# Singularitron_SD_Card_Module.net
KiCad netlist of a schematic drawn in EAGLE
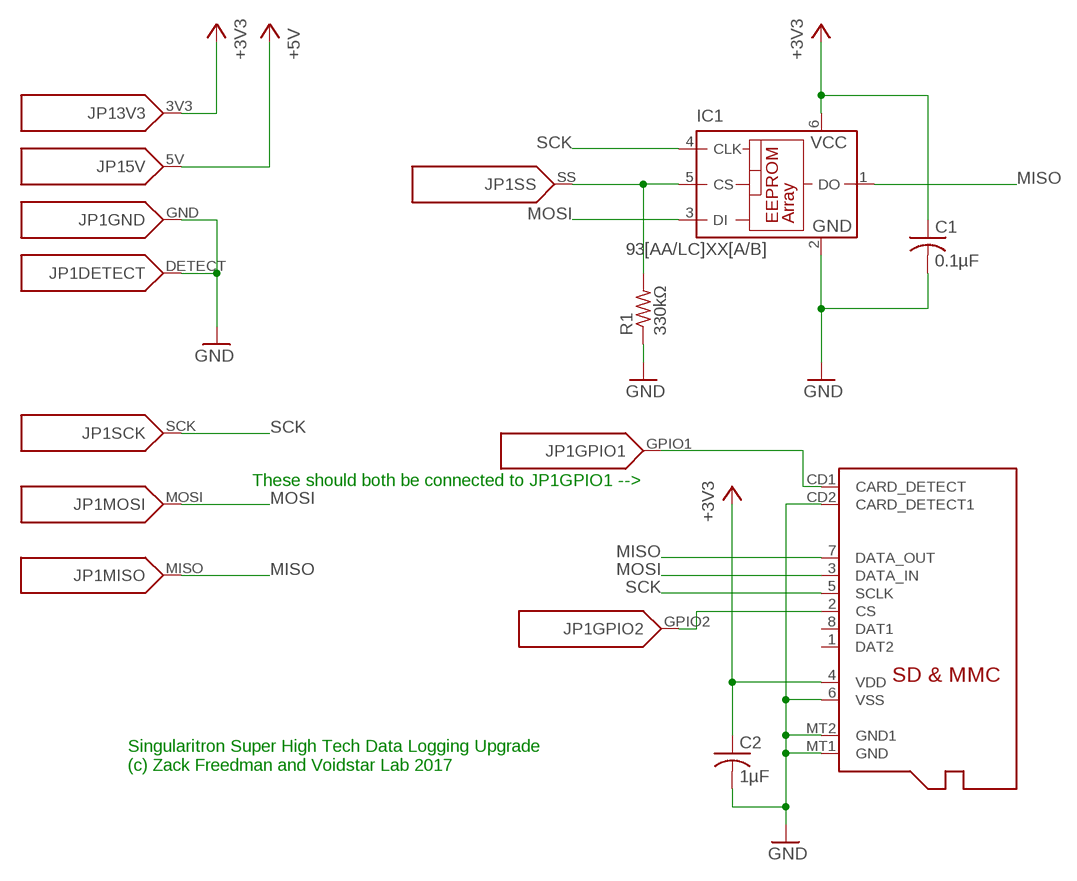
[diagram p0: schematic, sheet 1]

(export (version "E")
  (design (tool "Eeschema 10.0.6"))
  (components
    (comp (ref "C1")
      (value "0.1µF")
      (footprint "eagle-import:C0603")
      (libsource (lib "eagle-import") (part "C-USC0603"))
    )
    (comp (ref "C2")
      (value "1µF")
      (footprint "eagle-import:C0603")
      (libsource (lib "eagle-import") (part "C-USC0603"))
    )
    (comp (ref "IC1")
      (value "93[AA/LC]XX[A/B]")
      (footprint "eagle-import:SOT23-6")
      (fields (field (name "MPN") "93AA76AT-I/OT"))
      (libsource (lib "eagle-import") (part "9376?AAA"))
    )
    (comp (ref "JP1")
      (value "SINGULARITRON_CART_BASE")
      (footprint "eagle-import:SINGULARITRON_CART_BASE")
      (libsource (lib "eagle-import") (part "SINGULARITRON_CART_BASE"))
    )
    (comp (ref "JP2")
      (value "MICROSD")
      (footprint "eagle-import:MICROSD")
      (libsource (lib "eagle-import") (part "MICROSD"))
    )
    (comp (ref "R1")
      (value "330kΩ")
      (footprint "eagle-import:R0603")
      (libsource (lib "eagle-import") (part "R-US_R0603"))
    )
  )
  (nets
    (net (code "1") (name "+3V3") (class "Default")
      (node (ref "C1") (pin "1") (pinfunction "1_1") (pintype "passive"))
      (node (ref "C2") (pin "1") (pinfunction "1_1") (pintype "passive"))
      (node (ref "IC1") (pin "6") (pinfunction "VCC_6") (pintype "power_in"))
      (node (ref "JP1") (pin "3V3") (pinfunction "P$1_3V3") (pintype "bidirectional"))
      (node (ref "JP2") (pin "4") (pinfunction "VDD_4") (pintype "power_in"))
    )
    (net (code "2") (name "+5V") (class "Default")
      (node (ref "JP1") (pin "5V") (pinfunction "P$1_5V") (pintype "bidirectional"))
    )
    (net (code "3") (name "/MISO") (class "Default")
      (node (ref "IC1") (pin "1") (pinfunction "DO_1") (pintype "tri_state"))
      (node (ref "JP1") (pin "MISO") (pinfunction "P$1_MISO") (pintype "bidirectional"))
      (node (ref "JP2") (pin "7") (pinfunction "DATA_OUT_7") (pintype "output"))
    )
    (net (code "4") (name "/MOSI") (class "Default")
      (node (ref "IC1") (pin "3") (pinfunction "DI_3") (pintype "input"))
      (node (ref "JP1") (pin "MOSI") (pinfunction "P$1_MOSI") (pintype "bidirectional"))
      (node (ref "JP2") (pin "3") (pinfunction "DATA_IN_3") (pintype "input"))
    )
    (net (code "5") (name "/SCK") (class "Default")
      (node (ref "IC1") (pin "4") (pinfunction "CLK_4") (pintype "input"))
      (node (ref "JP1") (pin "SCK") (pinfunction "P$1_SCK") (pintype "bidirectional"))
      (node (ref "JP2") (pin "5") (pinfunction "SCLK_5") (pintype "input"))
    )
    (net (code "6") (name "GND") (class "Default")
      (node (ref "C1") (pin "2") (pinfunction "2_2") (pintype "passive"))
      (node (ref "C2") (pin "2") (pinfunction "2_2") (pintype "passive"))
      (node (ref "IC1") (pin "2") (pinfunction "GND_2") (pintype "power_in"))
      (node (ref "JP1") (pin "DETECT") (pinfunction "P$1_DETECT") (pintype "bidirectional"))
      (node (ref "JP1") (pin "GND") (pinfunction "P$1_GND") (pintype "bidirectional"))
      (node (ref "JP2") (pin "6") (pinfunction "VSS_6") (pintype "power_in"))
      (node (ref "JP2") (pin "CD2") (pinfunction "CARD_DETECT1_CD2") (pintype "passive"))
      (node (ref "JP2") (pin "MT1") (pinfunction "GND_MT1") (pintype "power_in"))
      (node (ref "JP2") (pin "MT2") (pinfunction "GND1_MT2") (pintype "power_in"))
      (node (ref "R1") (pin "1") (pinfunction "1_1") (pintype "passive"))
    )
    (net (code "7") (name "Net-(IC1-CS)") (class "Default")
      (node (ref "IC1") (pin "5") (pinfunction "CS_5") (pintype "input"))
      (node (ref "JP1") (pin "SS") (pinfunction "P$1_SS") (pintype "bidirectional"))
      (node (ref "R1") (pin "2") (pinfunction "2_2") (pintype "passive"))
    )
    (net (code "8") (name "Net-(JP1E-P$1)") (class "Default")
      (node (ref "JP1") (pin "GPIO1") (pinfunction "P$1_GPIO1") (pintype "bidirectional"))
      (node (ref "JP2") (pin "CD1") (pinfunction "CARD_DETECT_CD1") (pintype "passive"))
    )
    (net (code "9") (name "Net-(JP1F-P$1)") (class "Default")
      (node (ref "JP1") (pin "GPIO2") (pinfunction "P$1_GPIO2") (pintype "bidirectional"))
      (node (ref "JP2") (pin "2") (pinfunction "CS_2") (pintype "input"))
    )
    (net (code "10") (name "unconnected-(JP2-DAT1-Pad8)") (class "Default")
      (node (ref "JP2") (pin "8") (pinfunction "DAT1_8") (pintype "bidirectional"))
    )
    (net (code "11") (name "unconnected-(JP2-DAT2-Pad1)") (class "Default")
      (node (ref "JP2") (pin "1") (pinfunction "DAT2_1") (pintype "bidirectional"))
    )
  )
)
